# GSM_GPS.net
KiCad netlist of a schematic drawn in Altium Designer
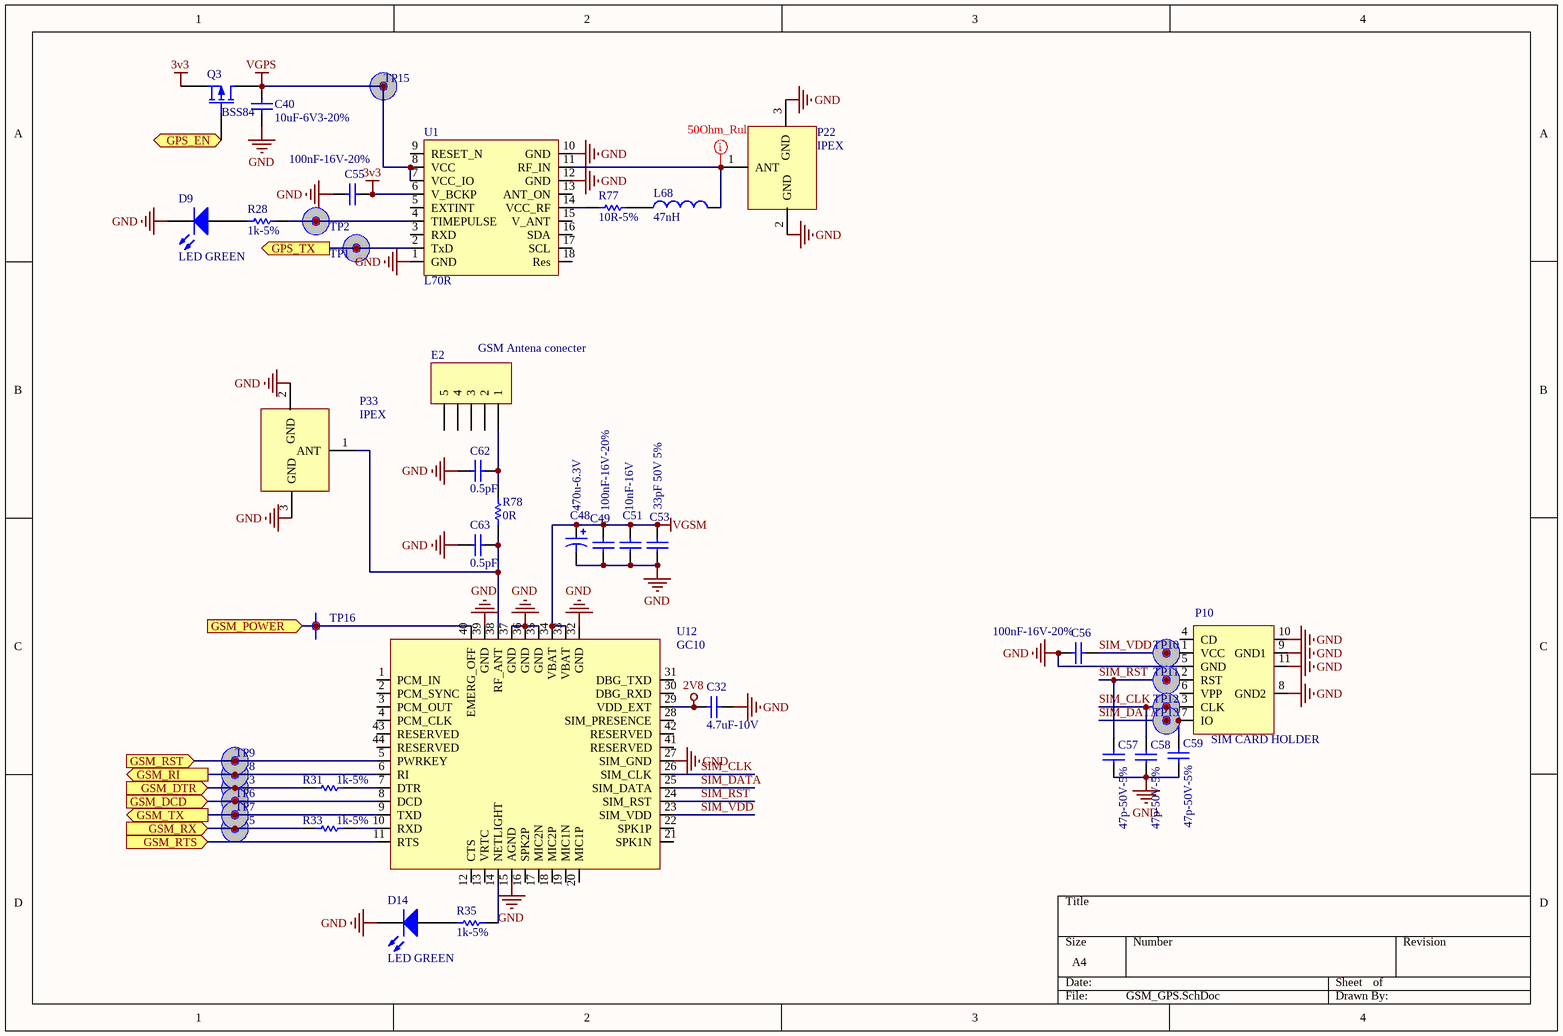
[diagram p0: GSM_GPS.SchDoc]

(export (version "E")
  (design (tool "Eeschema 10.0.6"))
  (components
    (comp (ref "C32")
      (value "4.7uF-10V")
      (footprint "C0603")
      (description "Non-Polarized Capacitor")
      (fields (field (name "DIGI-KEY PART NUMBER") "311-1371-1-ND") (field (name "MANUFACTURER") "Yageo"))
      (libsource (lib "Capacitor") (part "4.7uF-10V-C0805"))
    )
    (comp (ref "C40")
      (value "10uF-6V3-20%")
      (footprint "C0603")
      (description "CAP CER 10UF 6.3V 20% X5R 0603")
      (fields
        (field (name "MANUFACTURER") "Murata Electronics North America")
        (field (name "DIGI-KEY PART NUMBER") "490-3896-1-ND")
        (field (name "PUBLISHER") "Altium Limited")
      )
      (libsource (lib "Miscellaneous Devices") (part "Cap"))
    )
    (comp (ref "C48")
      (value "470u-6.3V")
      (footprint "C1812")
      (description "CAP CER 100UF 10V 20% X5R 1812")
      (fields
        (field (name "DIGI-KEY PART NUMBER") "445-7743-2-ND")
        (field (name "MANUFACTURER PART NUMBER") "C4532X5R1A107M")
        (field (name "PUBLISHER") "Altium Limited")
      )
      (libsource (lib "Miscellaneous Devices") (part "Cap Pol3"))
    )
    (comp (ref "C49")
      (value "100nF-16V-20%")
      (footprint "C0402")
      (description "CAP CER 0.1UF 16V Y5V 0402")
      (fields
        (field (name "MANUFACTURER") "Yageo")
        (field (name "DIGI-KEY PART NUMBER") "311-1047-1-ND")
        (field (name "PUBLISHER") "Altium Limited")
      )
      (libsource (lib "Miscellaneous Devices") (part "Cap"))
    )
    (comp (ref "C51")
      (value "10nF-16V")
      (footprint "C0402")
      (description "CAP CER 10000PF 16V 10% X7R 0402")
      (fields (field (name "DIGI-KEY PART NUMBER") "311-1042-2-ND") (field (name "MANUFACTURER") "Yageo"))
      (libsource (lib "Capacitor_0402") (part "10nF-16V-C0402-10%"))
    )
    (comp (ref "C53")
      (value "33pF 50V 5%")
      (footprint "C0402")
      (description "CAP CER 68PF 50V 5% NPO 0402")
      (fields (field (name "MANUFACTURER") "Yageo") (field (name "DIGI-KEY PART NUMBER") "311-1340-2-ND"))
      (libsource (lib "Miscellaneous Devices") (part "Cap"))
    )
    (comp (ref "C55")
      (value "100nF-16V-20%")
      (footprint "C0402")
      (description "CAP CER 0.1UF 16V Y5V 0402")
      (fields
        (field (name "MANUFACTURER") "Yageo")
        (field (name "DIGI-KEY PART NUMBER") "311-1047-1-ND")
        (field (name "PUBLISHER") "Altium Limited")
      )
      (libsource (lib "Miscellaneous Devices") (part "Cap"))
    )
    (comp (ref "C56")
      (value "100nF-16V-20%")
      (footprint "C0402")
      (description "CAP CER 0.1UF 16V Y5V 0402")
      (fields
        (field (name "MANUFACTURER") "Yageo")
        (field (name "DIGI-KEY PART NUMBER") "311-1047-1-ND")
        (field (name "PUBLISHER") "Altium Limited")
      )
      (libsource (lib "Miscellaneous Devices") (part "Cap"))
    )
    (comp (ref "C57")
      (value "47p-50V-5%")
      (footprint "C0402")
      (description "CAP CER 47PF 50V 5% NPO 0402")
      (fields
        (field (name "MANUFACTURER") "Yageo")
        (field (name "DIGI-KEY PART NUMBER") "311-1021-1-ND")
        (field (name "PUBLISHER") "Altium Limited")
      )
      (libsource (lib "Miscellaneous Devices") (part "Cap"))
    )
    (comp (ref "C58")
      (value "47p-50V-5%")
      (footprint "C0402")
      (description "CAP CER 47PF 50V 5% NPO 0402")
      (fields
        (field (name "MANUFACTURER") "Yageo")
        (field (name "DIGI-KEY PART NUMBER") "311-1021-1-ND")
        (field (name "PUBLISHER") "Altium Limited")
      )
      (libsource (lib "Miscellaneous Devices") (part "Cap"))
    )
    (comp (ref "C59")
      (value "47p-50V-5%")
      (footprint "C0402")
      (description "CAP CER 47PF 50V 5% NPO 0402")
      (fields
        (field (name "MANUFACTURER") "Yageo")
        (field (name "DIGI-KEY PART NUMBER") "311-1021-1-ND")
        (field (name "PUBLISHER") "Altium Limited")
      )
      (libsource (lib "Miscellaneous Devices") (part "Cap"))
    )
    (comp (ref "C62")
      (value "0.5pF")
      (footprint "C0402")
      (description "Non-Polarized Capacitor")
      (fields (field (name "DIGI-KEY PART NUMBER") "311-1094-1-ND") (field (name "MANUFACTURER") "Yageo"))
      (libsource (lib "Capacitor") (part "0.5pF-50V-C0805"))
    )
    (comp (ref "C63")
      (value "0.5pF")
      (footprint "C0402")
      (description "Non-Polarized Capacitor")
      (fields (field (name "DIGI-KEY PART NUMBER") "311-1094-1-ND") (field (name "MANUFACTURER") "Yageo"))
      (libsource (lib "Capacitor") (part "0.5pF-50V-C0805"))
    )
    (comp (ref "D9")
      (value "LED GREEN")
      (footprint "LED0603-G")
      (description "LED GREEN CLEAR THIN 0603 SMD")
      (fields
        (field (name "DIGI-KEY PART NUMBER") "160-1446-2-ND")
        (field (name "MANUFACTURER") "Lite-On Inc")
        (field (name "PUBLISHER") "Altium Limited")
      )
      (libsource (lib "Miscellaneous Devices") (part "LED2"))
    )
    (comp (ref "D14")
      (value "LED GREEN")
      (footprint "LED0603-G")
      (description "LED GREEN CLEAR THIN 0603 SMD")
      (fields
        (field (name "DIGI-KEY PART NUMBER") "160-1446-2-ND")
        (field (name "MANUFACTURER") "Lite-On Inc")
        (field (name "PUBLISHER") "Altium Limited")
      )
      (libsource (lib "Miscellaneous Devices") (part "LED2"))
    )
    (comp (ref "E2")
      (value "GSM Antena conecter")
      (footprint "A10343-GSM850/900/1800/1900/WCDMA")
      (description "Header, 5-Pin")
      (fields (field (name "PUBLISHER") "Altium Limited"))
      (libsource (lib "Miscellaneous Connectors") (part "Header 5"))
    )
    (comp (ref "L68")
      (value "47nH")
      (footprint "C0603")
      (description "Inductor")
      (fields (field (name "PUBLISHER") "Altium Limited"))
      (libsource (lib "Miscellaneous Devices") (part "Inductor"))
    )
    (comp (ref "P10")
      (value "SIM CARD HOLDER")
      (footprint "SIM MF01-412-063X")
      (description "SIM _CONNECTOR_410108105011-2LF")
      (fields (field (name "MANUFACTURER") "Tyrone"))
      (libsource (lib "Schlib1") (part "SIM CARD"))
    )
    (comp (ref "P22") (value "IPEX") (footprint "IPEX") (libsource (lib "") (part "IPEX_1")))
    (comp (ref "P33") (value "IPEX") (footprint "IPEX") (libsource (lib "Schlib1") (part "IPEX")))
    (comp (ref "Q3")
      (value "BSS84")
      (footprint "SOT23-3")
      (description "MOSFET P-CH 50V 130MA SOT23-3")
      (fields
        (field (name "DIGI-KEY PART NUMBER") "BSS84-FDITR-ND")
        (field (name "MANUFACTURER") "Diodes Inc")
        (field (name "PUBLISHER") "Altium Limited")
      )
      (libsource (lib "Miscellaneous Devices") (part "MOSFET-P"))
    )
    (comp (ref "R28")
      (value "1k-5%")
      (footprint "R0402")
      (description "RES 1.0K OHM 1/16W 5% 0402 SMD")
      (fields
        (field (name "DIGI-KEY PART NUMBER") "311-1.0KJRCT-ND")
        (field (name "MANUFACTURER") "Yageo")
        (field (name "PUBLISHER") "Altium Limited")
      )
      (libsource (lib "Miscellaneous Devices") (part "Res1"))
    )
    (comp (ref "R31")
      (value "1k-5%")
      (footprint "R0402")
      (description "RES 1.0K OHM 1/16W 5% 0402 SMD")
      (fields
        (field (name "DIGI-KEY PART NUMBER") "311-1.0KJRCT-ND")
        (field (name "MANUFACTURER") "Yageo")
        (field (name "PUBLISHER") "Altium Limited")
      )
      (libsource (lib "Miscellaneous Devices") (part "Res1"))
    )
    (comp (ref "R33")
      (value "1k-5%")
      (footprint "R0402")
      (description "RES 1.0K OHM 1/16W 5% 0402 SMD")
      (fields
        (field (name "DIGI-KEY PART NUMBER") "311-1.0KJRCT-ND")
        (field (name "MANUFACTURER") "Yageo")
        (field (name "PUBLISHER") "Altium Limited")
      )
      (libsource (lib "Miscellaneous Devices") (part "Res1"))
    )
    (comp (ref "R35")
      (value "1k-5%")
      (footprint "R0402")
      (description "RES 1.0K OHM 1/16W 5% 0402 SMD")
      (fields
        (field (name "DIGI-KEY PART NUMBER") "311-1.0KJRCT-ND")
        (field (name "MANUFACTURER") "Yageo")
        (field (name "PUBLISHER") "Altium Limited")
      )
      (libsource (lib "Miscellaneous Devices") (part "Res1"))
    )
    (comp (ref "R77")
      (value "10R-5%")
      (footprint "R0402")
      (description "RES 10 OHM 1/16W 5% 0402 SMD")
      (fields (field (name "DIGI-KEY PART NUMBER") "311-10JRTR-ND") (field (name "MANUFACTURER") "Yageo"))
      (libsource (lib "Resistor_0402") (part "10R-5%-R0402"))
    )
    (comp (ref "R78") (value "0R") (footprint "R0402") (libsource (lib "All_Resistor") (part "0R-0805")))
    (comp (ref "TP1") (value "TP") (footprint "test_point") (libsource (lib "Lib") (part "TP")))
    (comp (ref "TP2") (value "TP") (footprint "test_point") (libsource (lib "Lib") (part "TP")))
    (comp (ref "TP3") (value "TP") (footprint "test_point") (libsource (lib "Lib") (part "TP")))
    (comp (ref "TP5") (value "TP") (footprint "test_point") (libsource (lib "Lib") (part "TP")))
    (comp (ref "TP6") (value "TP") (footprint "test_point") (libsource (lib "Lib") (part "TP")))
    (comp (ref "TP7") (value "TP") (footprint "test_point") (libsource (lib "Lib") (part "TP")))
    (comp (ref "TP8") (value "TP") (footprint "test_point") (libsource (lib "Lib") (part "TP")))
    (comp (ref "TP9") (value "TP") (footprint "test_point") (libsource (lib "Lib") (part "TP")))
    (comp (ref "TP10") (value "TP") (footprint "test_point") (libsource (lib "Lib") (part "TP")))
    (comp (ref "TP11") (value "TP") (footprint "test_point") (libsource (lib "Lib") (part "TP")))
    (comp (ref "TP12") (value "TP") (footprint "test_point") (libsource (lib "Lib") (part "TP")))
    (comp (ref "TP13") (value "TP") (footprint "test_point") (libsource (lib "Lib") (part "TP")))
    (comp (ref "TP15") (value "TP") (footprint "test_point") (libsource (lib "Lib") (part "TP")))
    (comp (ref "TP16") (value "TP") (footprint "test_point") (libsource (lib "") (part "TP_1")))
    (comp (ref "U1") (value "L70R") (footprint "MAX7") (libsource (lib "U-Blox") (part "MAX-7")))
    (comp (ref "U12") (value "GC10") (footprint "GC10") (libsource (lib "GSM_MODULE") (part "GC10")))
  )
  (nets
    (net (code "1") (name "/GPS_EN") (class "Default")
      (node (ref "Q3") (pin "1") (pinfunction "G_1") (pintype "passive"))
    )
    (net (code "2") (name "/GPS_TX") (class "Default")
      (node (ref "TP1") (pin "1") (pinfunction "TP_1") (pintype "passive"))
      (node (ref "U1") (pin "2") (pinfunction "TxD_2") (pintype "passive"))
    )
    (net (code "3") (name "/GSM_DCD") (class "Default")
      (node (ref "TP6") (pin "1") (pinfunction "TP_1") (pintype "passive"))
      (node (ref "U12") (pin "8") (pinfunction "DCD_8") (pintype "passive"))
    )
    (net (code "4") (name "/GSM_DTR") (class "Default")
      (node (ref "R31") (pin "2") (pinfunction "2_2") (pintype "passive"))
      (node (ref "TP3") (pin "1") (pinfunction "TP_1") (pintype "passive"))
    )
    (net (code "5") (name "/GSM_POWER") (class "Default")
      (node (ref "TP16") (pin "1") (pinfunction "TP_1") (pintype "passive"))
      (node (ref "U12") (pin "40") (pinfunction "EMERG_OFF_40") (pintype "passive"))
    )
    (net (code "6") (name "/GSM_RI") (class "Default")
      (node (ref "TP8") (pin "1") (pinfunction "TP_1") (pintype "passive"))
      (node (ref "U12") (pin "6") (pinfunction "RI_6") (pintype "passive"))
    )
    (net (code "7") (name "/GSM_RST") (class "Default")
      (node (ref "TP9") (pin "1") (pinfunction "TP_1") (pintype "passive"))
      (node (ref "U12") (pin "5") (pinfunction "PWRKEY_5") (pintype "passive"))
    )
    (net (code "8") (name "/GSM_RTS") (class "Default")
      (node (ref "U12") (pin "11") (pinfunction "RTS_11") (pintype "passive"))
    )
    (net (code "9") (name "/GSM_RX") (class "Default")
      (node (ref "R33") (pin "2") (pinfunction "2_2") (pintype "passive"))
      (node (ref "TP5") (pin "1") (pinfunction "TP_1") (pintype "passive"))
    )
    (net (code "10") (name "/GSM_TX") (class "Default")
      (node (ref "TP7") (pin "1") (pinfunction "TP_1") (pintype "passive"))
      (node (ref "U12") (pin "9") (pinfunction "TXD_9") (pintype "passive"))
    )
    (net (code "11") (name "/SIM_CLK") (class "Default")
      (node (ref "C58") (pin "2") (pinfunction "2_2") (pintype "passive"))
      (node (ref "P10") (pin "3") (pinfunction "CLK_3") (pintype "passive"))
      (node (ref "TP12") (pin "1") (pinfunction "TP_1") (pintype "passive"))
      (node (ref "U12") (pin "26") (pinfunction "SIM_CLK_26") (pintype "passive"))
    )
    (net (code "12") (name "/SIM_DATA") (class "Default")
      (node (ref "C59") (pin "2") (pinfunction "2_2") (pintype "passive"))
      (node (ref "P10") (pin "7") (pinfunction "IO_7") (pintype "passive"))
      (node (ref "TP13") (pin "1") (pinfunction "TP_1") (pintype "passive"))
      (node (ref "U12") (pin "25") (pinfunction "SIM_DATA_25") (pintype "passive"))
    )
    (net (code "13") (name "/SIM_RST") (class "Default")
      (node (ref "C57") (pin "2") (pinfunction "2_2") (pintype "passive"))
      (node (ref "P10") (pin "2") (pinfunction "RST_2") (pintype "passive"))
      (node (ref "TP11") (pin "1") (pinfunction "TP_1") (pintype "passive"))
      (node (ref "U12") (pin "24") (pinfunction "SIM_RST_24") (pintype "passive"))
    )
    (net (code "14") (name "/SIM_VDD") (class "Default")
      (node (ref "C56") (pin "1") (pinfunction "1_1") (pintype "passive"))
      (node (ref "P10") (pin "1") (pinfunction "VCC_1") (pintype "passive"))
      (node (ref "TP10") (pin "1") (pinfunction "TP_1") (pintype "passive"))
      (node (ref "U12") (pin "23") (pinfunction "SIM_VDD_23") (pintype "passive"))
    )
    (net (code "15") (name "2V8") (class "Default")
      (node (ref "C32") (pin "2") (pinfunction "2_2") (pintype "passive"))
      (node (ref "U12") (pin "29") (pinfunction "VDD_EXT_29") (pintype "passive"))
    )
    (net (code "16") (name "3v3") (class "Default")
      (node (ref "C55") (pin "1") (pinfunction "1_1") (pintype "passive"))
      (node (ref "Q3") (pin "2") (pinfunction "S_2") (pintype "passive"))
      (node (ref "U1") (pin "6") (pinfunction "V_BCKP_6") (pintype "passive"))
    )
    (net (code "17") (name "GND") (class "Default")
      (node (ref "C32") (pin "1") (pinfunction "1_1") (pintype "passive"))
      (node (ref "C40") (pin "1") (pinfunction "1_1") (pintype "passive"))
      (node (ref "C48") (pin "2") (pinfunction "2_2") (pintype "passive"))
      (node (ref "C49") (pin "2") (pinfunction "2_2") (pintype "passive"))
      (node (ref "C51") (pin "1") (pinfunction "1_1") (pintype "passive"))
      (node (ref "C53") (pin "2") (pinfunction "2_2") (pintype "passive"))
      (node (ref "C55") (pin "2") (pinfunction "2_2") (pintype "passive"))
      (node (ref "C56") (pin "2") (pinfunction "2_2") (pintype "passive"))
      (node (ref "C57") (pin "1") (pinfunction "1_1") (pintype "passive"))
      (node (ref "C58") (pin "1") (pinfunction "1_1") (pintype "passive"))
      (node (ref "C59") (pin "1") (pinfunction "1_1") (pintype "passive"))
      (node (ref "C62") (pin "1") (pinfunction "1_1") (pintype "passive"))
      (node (ref "C63") (pin "1") (pinfunction "1_1") (pintype "passive"))
      (node (ref "D14") (pin "2") (pinfunction "K_2") (pintype "passive"))
      (node (ref "D9") (pin "2") (pinfunction "K_2") (pintype "passive"))
      (node (ref "P10") (pin "10") (pinfunction "GND3_10") (pintype "passive"))
      (node (ref "P10") (pin "11") (pinfunction "GND4_11") (pintype "passive"))
      (node (ref "P10") (pin "5") (pinfunction "GND_5") (pintype "passive"))
      (node (ref "P10") (pin "8") (pinfunction "GND2_8") (pintype "passive"))
      (node (ref "P10") (pin "9") (pinfunction "GND1_9") (pintype "passive"))
      (node (ref "P22") (pin "2") (pinfunction "GND_2") (pintype "passive"))
      (node (ref "P22") (pin "3") (pinfunction "GND_3") (pintype "passive"))
      (node (ref "P33") (pin "2") (pinfunction "GND_2") (pintype "passive"))
      (node (ref "P33") (pin "3") (pinfunction "GND_3") (pintype "passive"))
      (node (ref "U1") (pin "1") (pinfunction "GND_1") (pintype "passive"))
      (node (ref "U1") (pin "10") (pinfunction "GND_10") (pintype "passive"))
      (node (ref "U1") (pin "12") (pinfunction "GND_12") (pintype "passive"))
      (node (ref "U12") (pin "15") (pinfunction "AGND_15") (pintype "passive"))
      (node (ref "U12") (pin "27") (pinfunction "SIM_GND_27") (pintype "passive"))
      (node (ref "U12") (pin "32") (pinfunction "GND_32") (pintype "passive"))
      (node (ref "U12") (pin "35") (pinfunction "GND_35") (pintype "passive"))
      (node (ref "U12") (pin "36") (pinfunction "GND_36") (pintype "passive"))
      (node (ref "U12") (pin "37") (pinfunction "GND_37") (pintype "passive"))
      (node (ref "U12") (pin "39") (pinfunction "GND_39") (pintype "passive"))
    )
    (net (code "18") (name "Net-(C62-Pad2)") (class "Default")
      (node (ref "C62") (pin "2") (pinfunction "2_2") (pintype "passive"))
      (node (ref "E2") (pin "1") (pinfunction "1_1") (pintype "passive"))
      (node (ref "R78") (pin "2") (pinfunction "2_2") (pintype "passive"))
    )
    (net (code "19") (name "Net-(D9-A)") (class "Default")
      (node (ref "D9") (pin "1") (pinfunction "A_1") (pintype "passive"))
      (node (ref "R28") (pin "2") (pinfunction "2_2") (pintype "passive"))
    )
    (net (code "20") (name "Net-(D14-A)") (class "Default")
      (node (ref "D14") (pin "1") (pinfunction "A_1") (pintype "passive"))
      (node (ref "R35") (pin "1") (pinfunction "1_1") (pintype "passive"))
    )
    (net (code "21") (name "Net-(L68-Pad1)") (class "Default")
      (node (ref "L68") (pin "1") (pinfunction "1_1") (pintype "passive"))
      (node (ref "R77") (pin "1") (pinfunction "1_1") (pintype "passive"))
    )
    (net (code "22") (name "Net-(P22-ANT)") (class "Default")
      (node (ref "L68") (pin "2") (pinfunction "2_2") (pintype "passive"))
      (node (ref "P22") (pin "1") (pinfunction "ANT_1") (pintype "passive"))
      (node (ref "U1") (pin "11") (pinfunction "RF_IN_11") (pintype "passive"))
    )
    (net (code "23") (name "Net-(P33-ANT)") (class "Default")
      (node (ref "C63") (pin "2") (pinfunction "2_2") (pintype "passive"))
      (node (ref "P33") (pin "1") (pinfunction "ANT_1") (pintype "passive"))
      (node (ref "R78") (pin "1") (pinfunction "1_1") (pintype "passive"))
      (node (ref "U12") (pin "38") (pinfunction "RF_ANT_38") (pintype "passive"))
    )
    (net (code "24") (name "Net-(TP2-TP)") (class "Default")
      (node (ref "R28") (pin "1") (pinfunction "1_1") (pintype "passive"))
      (node (ref "TP2") (pin "1") (pinfunction "TP_1") (pintype "passive"))
      (node (ref "U1") (pin "4") (pinfunction "TIMEPULSE_4") (pintype "passive"))
    )
    (net (code "25") (name "Net-(U1-VCC_RF)") (class "Default")
      (node (ref "R77") (pin "2") (pinfunction "2_2") (pintype "passive"))
      (node (ref "U1") (pin "14") (pinfunction "VCC_RF_14") (pintype "passive"))
    )
    (net (code "26") (name "Net-(U12-DTR)") (class "Default")
      (node (ref "R31") (pin "1") (pinfunction "1_1") (pintype "passive"))
      (node (ref "U12") (pin "7") (pinfunction "DTR_7") (pintype "passive"))
    )
    (net (code "27") (name "Net-(U12-NETLIGHT)") (class "Default")
      (node (ref "R35") (pin "2") (pinfunction "2_2") (pintype "passive"))
      (node (ref "U12") (pin "14") (pinfunction "NETLIGHT_14") (pintype "passive"))
    )
    (net (code "28") (name "Net-(U12-RXD)") (class "Default")
      (node (ref "R33") (pin "1") (pinfunction "1_1") (pintype "passive"))
      (node (ref "U12") (pin "10") (pinfunction "RXD_10") (pintype "passive"))
    )
    (net (code "29") (name "VGPS") (class "Default")
      (node (ref "C40") (pin "2") (pinfunction "2_2") (pintype "passive"))
      (node (ref "Q3") (pin "3") (pinfunction "D_3") (pintype "passive"))
      (node (ref "TP15") (pin "1") (pinfunction "TP_1") (pintype "passive"))
      (node (ref "U1") (pin "7") (pinfunction "VCC_IO_7") (pintype "passive"))
      (node (ref "U1") (pin "8") (pinfunction "VCC_8") (pintype "passive"))
    )
    (net (code "30") (name "VGSM") (class "Default")
      (node (ref "C48") (pin "1") (pinfunction "1_1") (pintype "passive"))
      (node (ref "C49") (pin "1") (pinfunction "1_1") (pintype "passive"))
      (node (ref "C51") (pin "2") (pinfunction "2_2") (pintype "passive"))
      (node (ref "C53") (pin "1") (pinfunction "1_1") (pintype "passive"))
      (node (ref "U12") (pin "33") (pinfunction "VBAT_33") (pintype "passive"))
      (node (ref "U12") (pin "34") (pinfunction "VBAT_34") (pintype "passive"))
    )
    (net (code "31") (name "unconnected-(E2-Pad2)") (class "Default")
      (node (ref "E2") (pin "2") (pinfunction "2_2") (pintype "passive"))
    )
    (net (code "32") (name "unconnected-(E2-Pad3)") (class "Default")
      (node (ref "E2") (pin "3") (pinfunction "3_3") (pintype "passive"))
    )
    (net (code "33") (name "unconnected-(E2-Pad4)") (class "Default")
      (node (ref "E2") (pin "4") (pinfunction "4_4") (pintype "passive"))
    )
    (net (code "34") (name "unconnected-(E2-Pad5)") (class "Default")
      (node (ref "E2") (pin "5") (pinfunction "5_5") (pintype "passive"))
    )
    (net (code "35") (name "unconnected-(P10-CD-Pad4)") (class "Default")
      (node (ref "P10") (pin "4") (pinfunction "CD_4") (pintype "passive"))
    )
    (net (code "36") (name "unconnected-(P10-VPP-Pad6)") (class "Default")
      (node (ref "P10") (pin "6") (pinfunction "VPP_6") (pintype "passive"))
    )
    (net (code "37") (name "unconnected-(U1-ANT_ON-Pad13)") (class "Default")
      (node (ref "U1") (pin "13") (pinfunction "ANT_ON_13") (pintype "passive"))
    )
    (net (code "38") (name "unconnected-(U1-EXTINT-Pad5)") (class "Default")
      (node (ref "U1") (pin "5") (pinfunction "EXTINT_5") (pintype "passive"))
    )
    (net (code "39") (name "unconnected-(U1-RESET_N-Pad9)") (class "Default")
      (node (ref "U1") (pin "9") (pinfunction "RESET_N_9") (pintype "passive"))
    )
    (net (code "40") (name "unconnected-(U1-RXD-Pad3)") (class "Default")
      (node (ref "U1") (pin "3") (pinfunction "RXD_3") (pintype "passive"))
    )
    (net (code "41") (name "unconnected-(U1-Res-Pad18)") (class "Default")
      (node (ref "U1") (pin "18") (pinfunction "Res_18") (pintype "passive"))
    )
    (net (code "42") (name "unconnected-(U1-SCL-Pad17)") (class "Default")
      (node (ref "U1") (pin "17") (pinfunction "SCL_17") (pintype "passive"))
    )
    (net (code "43") (name "unconnected-(U1-SDA-Pad16)") (class "Default")
      (node (ref "U1") (pin "16") (pinfunction "SDA_16") (pintype "passive"))
    )
    (net (code "44") (name "unconnected-(U1-V_ANT-Pad15)") (class "Default")
      (node (ref "U1") (pin "15") (pinfunction "V_ANT_15") (pintype "passive"))
    )
    (net (code "45") (name "unconnected-(U12-CTS-Pad12)") (class "Default")
      (node (ref "U12") (pin "12") (pinfunction "CTS_12") (pintype "passive"))
    )
    (net (code "46") (name "unconnected-(U12-DBG_RXD-Pad30)") (class "Default")
      (node (ref "U12") (pin "30") (pinfunction "DBG_RXD_30") (pintype "passive"))
    )
    (net (code "47") (name "unconnected-(U12-DBG_TXD-Pad31)") (class "Default")
      (node (ref "U12") (pin "31") (pinfunction "DBG_TXD_31") (pintype "passive"))
    )
    (net (code "48") (name "unconnected-(U12-MIC1N-Pad19)") (class "Default")
      (node (ref "U12") (pin "19") (pinfunction "MIC1N_19") (pintype "passive"))
    )
    (net (code "49") (name "unconnected-(U12-MIC1P-Pad20)") (class "Default")
      (node (ref "U12") (pin "20") (pinfunction "MIC1P_20") (pintype "passive"))
    )
    (net (code "50") (name "unconnected-(U12-MIC2N-Pad17)") (class "Default")
      (node (ref "U12") (pin "17") (pinfunction "MIC2N_17") (pintype "passive"))
    )
    (net (code "51") (name "unconnected-(U12-MIC2P-Pad18)") (class "Default")
      (node (ref "U12") (pin "18") (pinfunction "MIC2P_18") (pintype "passive"))
    )
    (net (code "52") (name "unconnected-(U12-PCM_CLK-Pad4)") (class "Default")
      (node (ref "U12") (pin "4") (pinfunction "PCM_CLK_4") (pintype "passive"))
    )
    (net (code "53") (name "unconnected-(U12-PCM_IN-Pad1)") (class "Default")
      (node (ref "U12") (pin "1") (pinfunction "PCM_IN_1") (pintype "passive"))
    )
    (net (code "54") (name "unconnected-(U12-PCM_OUT-Pad3)") (class "Default")
      (node (ref "U12") (pin "3") (pinfunction "PCM_OUT_3") (pintype "passive"))
    )
    (net (code "55") (name "unconnected-(U12-PCM_SYNC-Pad2)") (class "Default")
      (node (ref "U12") (pin "2") (pinfunction "PCM_SYNC_2") (pintype "passive"))
    )
    (net (code "56") (name "unconnected-(U12-RESERVED-Pad41)") (class "Default")
      (node (ref "U12") (pin "41") (pinfunction "RESERVED_41") (pintype "passive"))
    )
    (net (code "57") (name "unconnected-(U12-RESERVED-Pad42)") (class "Default")
      (node (ref "U12") (pin "42") (pinfunction "RESERVED_42") (pintype "passive"))
    )
    (net (code "58") (name "unconnected-(U12-RESERVED-Pad43)") (class "Default")
      (node (ref "U12") (pin "43") (pinfunction "RESERVED_43") (pintype "passive"))
    )
    (net (code "59") (name "unconnected-(U12-RESERVED-Pad44)") (class "Default")
      (node (ref "U12") (pin "44") (pinfunction "RESERVED_44") (pintype "passive"))
    )
    (net (code "60") (name "unconnected-(U12-SIM_PRESENCE-Pad28)") (class "Default")
      (node (ref "U12") (pin "28") (pinfunction "SIM_PRESENCE_28") (pintype "passive"))
    )
    (net (code "61") (name "unconnected-(U12-SPK1N-Pad21)") (class "Default")
      (node (ref "U12") (pin "21") (pinfunction "SPK1N_21") (pintype "passive"))
    )
    (net (code "62") (name "unconnected-(U12-SPK1P-Pad22)") (class "Default")
      (node (ref "U12") (pin "22") (pinfunction "SPK1P_22") (pintype "passive"))
    )
    (net (code "63") (name "unconnected-(U12-SPK2P-Pad16)") (class "Default")
      (node (ref "U12") (pin "16") (pinfunction "SPK2P_16") (pintype "passive"))
    )
    (net (code "64") (name "unconnected-(U12-VRTC-Pad13)") (class "Default")
      (node (ref "U12") (pin "13") (pinfunction "VRTC_13") (pintype "passive"))
    )
  )
)
